# input_buff.net
KiCad netlist of a schematic drawn in EAGLE
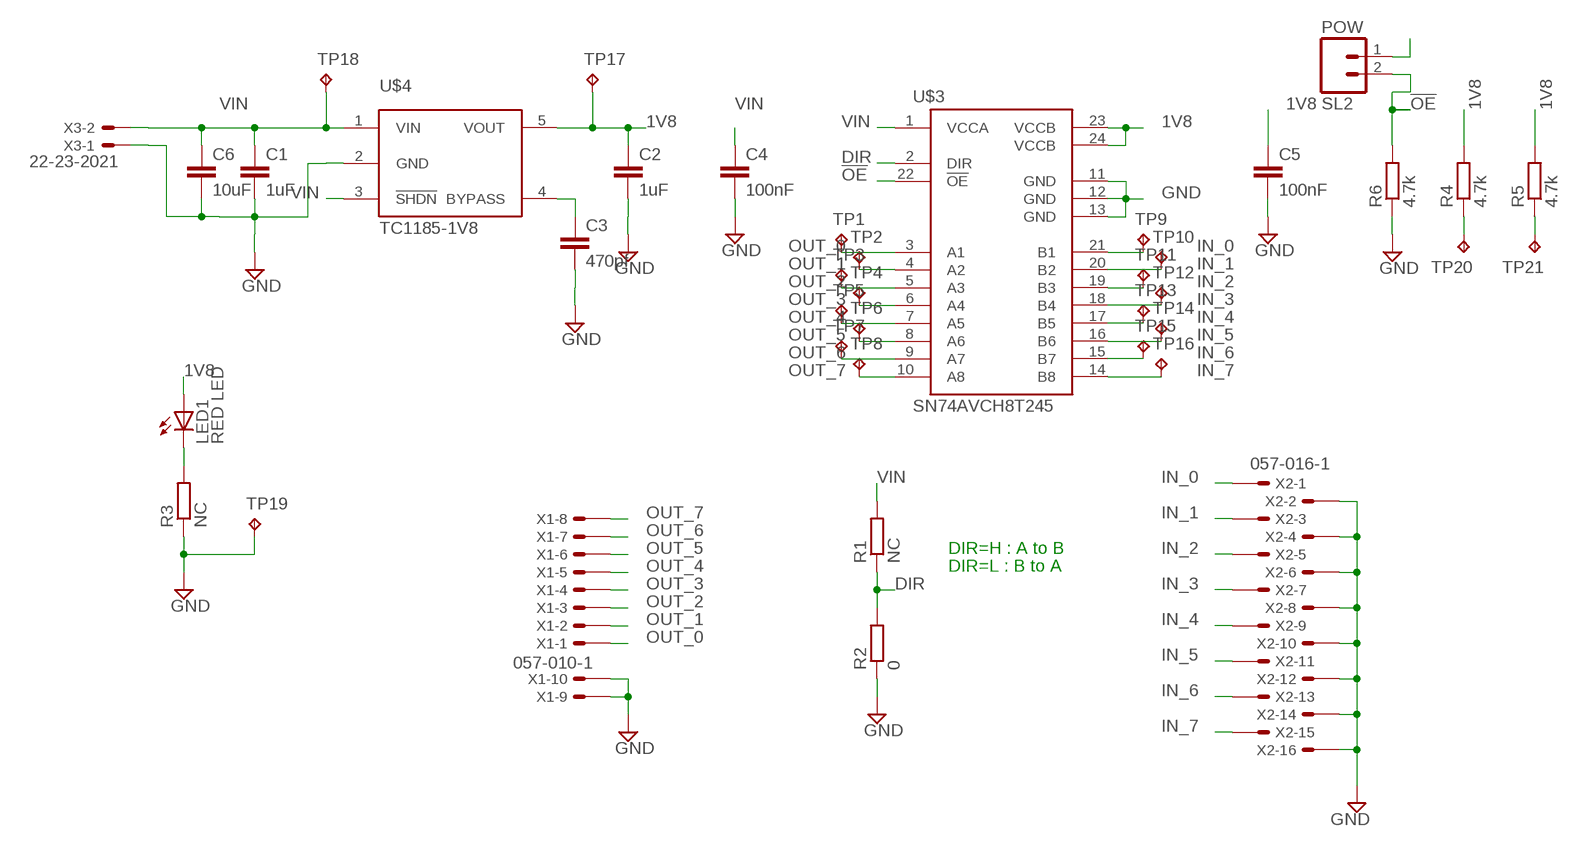
[diagram p0: schematic, sheet 1]

(export (version "E")
  (design (tool "Eeschema 10.0.6"))
  (components
    (comp (ref "C1")
      (value "1uF")
      (footprint "eagle-import:C0805")
      (libsource (lib "eagle-import") (part "C-EUC0805"))
    )
    (comp (ref "C2")
      (value "1uF")
      (footprint "eagle-import:C0805")
      (libsource (lib "eagle-import") (part "C-EUC0805"))
    )
    (comp (ref "C3")
      (value "470pf")
      (footprint "eagle-import:C0805")
      (libsource (lib "eagle-import") (part "C-EUC0805"))
    )
    (comp (ref "C4")
      (value "100nF")
      (footprint "eagle-import:C0805")
      (libsource (lib "eagle-import") (part "C-EUC0805"))
    )
    (comp (ref "C5")
      (value "100nF")
      (footprint "eagle-import:C0805")
      (libsource (lib "eagle-import") (part "C-EUC0805"))
    )
    (comp (ref "C6")
      (value "10uF")
      (footprint "eagle-import:C1210")
      (libsource (lib "eagle-import") (part "C-EUC1210"))
    )
    (comp (ref "LED1")
      (value "RED LED")
      (footprint "eagle-import:CHIPLED_0805")
      (libsource (lib "eagle-import") (part "LEDCHIPLED_0805"))
    )
    (comp (ref "R1")
      (value "NC")
      (footprint "eagle-import:M0805")
      (libsource (lib "eagle-import") (part "R-EU_M0805"))
    )
    (comp (ref "R2")
      (value "0")
      (footprint "eagle-import:M0805")
      (libsource (lib "eagle-import") (part "R-EU_M0805"))
    )
    (comp (ref "R3")
      (value "NC")
      (footprint "eagle-import:M0805")
      (libsource (lib "eagle-import") (part "R-EU_M0805"))
    )
    (comp (ref "R4")
      (value "4.7k")
      (footprint "eagle-import:M0805")
      (libsource (lib "eagle-import") (part "R-EU_M0805"))
    )
    (comp (ref "R5")
      (value "4.7k")
      (footprint "eagle-import:M0805")
      (libsource (lib "eagle-import") (part "R-EU_M0805"))
    )
    (comp (ref "R6")
      (value "4.7k")
      (footprint "eagle-import:M0805")
      (libsource (lib "eagle-import") (part "R-EU_M0805"))
    )
    (comp (ref "SL2")
      (value "POW")
      (footprint "eagle-import:02P")
      (fields (field (name "OC_FARNELL") "unknown") (field (name "OC_NEWARK") "unknown"))
      (libsource (lib "eagle-import") (part "M02"))
    )
    (comp (ref "TP1")
      (value "TPTP10R")
      (footprint "eagle-import:TP10R")
      (libsource (lib "eagle-import") (part "TPTP10R"))
    )
    (comp (ref "TP2")
      (value "TPTP10R")
      (footprint "eagle-import:TP10R")
      (libsource (lib "eagle-import") (part "TPTP10R"))
    )
    (comp (ref "TP3")
      (value "TPTP10R")
      (footprint "eagle-import:TP10R")
      (libsource (lib "eagle-import") (part "TPTP10R"))
    )
    (comp (ref "TP4")
      (value "TPTP10R")
      (footprint "eagle-import:TP10R")
      (libsource (lib "eagle-import") (part "TPTP10R"))
    )
    (comp (ref "TP5")
      (value "TPTP10R")
      (footprint "eagle-import:TP10R")
      (libsource (lib "eagle-import") (part "TPTP10R"))
    )
    (comp (ref "TP6")
      (value "TPTP10R")
      (footprint "eagle-import:TP10R")
      (libsource (lib "eagle-import") (part "TPTP10R"))
    )
    (comp (ref "TP7")
      (value "TPTP10R")
      (footprint "eagle-import:TP10R")
      (libsource (lib "eagle-import") (part "TPTP10R"))
    )
    (comp (ref "TP8")
      (value "TPTP10R")
      (footprint "eagle-import:TP10R")
      (libsource (lib "eagle-import") (part "TPTP10R"))
    )
    (comp (ref "TP9")
      (value "TPTP10R")
      (footprint "eagle-import:TP10R")
      (libsource (lib "eagle-import") (part "TPTP10R"))
    )
    (comp (ref "TP10")
      (value "TPTP10R")
      (footprint "eagle-import:TP10R")
      (libsource (lib "eagle-import") (part "TPTP10R"))
    )
    (comp (ref "TP11")
      (value "TPTP10R")
      (footprint "eagle-import:TP10R")
      (libsource (lib "eagle-import") (part "TPTP10R"))
    )
    (comp (ref "TP12")
      (value "TPTP10R")
      (footprint "eagle-import:TP10R")
      (libsource (lib "eagle-import") (part "TPTP10R"))
    )
    (comp (ref "TP13")
      (value "TPTP10R")
      (footprint "eagle-import:TP10R")
      (libsource (lib "eagle-import") (part "TPTP10R"))
    )
    (comp (ref "TP14")
      (value "TPTP10R")
      (footprint "eagle-import:TP10R")
      (libsource (lib "eagle-import") (part "TPTP10R"))
    )
    (comp (ref "TP15")
      (value "TPTP10R")
      (footprint "eagle-import:TP10R")
      (libsource (lib "eagle-import") (part "TPTP10R"))
    )
    (comp (ref "TP16")
      (value "TPTP10R")
      (footprint "eagle-import:TP10R")
      (libsource (lib "eagle-import") (part "TPTP10R"))
    )
    (comp (ref "TP17")
      (value "TPTP10R")
      (footprint "eagle-import:TP10R")
      (libsource (lib "eagle-import") (part "TPTP10R"))
    )
    (comp (ref "TP18")
      (value "TPTP10R")
      (footprint "eagle-import:TP10R")
      (libsource (lib "eagle-import") (part "TPTP10R"))
    )
    (comp (ref "TP19")
      (value "TPTP10R")
      (footprint "eagle-import:TP10R")
      (libsource (lib "eagle-import") (part "TPTP10R"))
    )
    (comp (ref "TP20")
      (value "TPTP10R")
      (footprint "eagle-import:TP10R")
      (libsource (lib "eagle-import") (part "TPTP10R"))
    )
    (comp (ref "TP21")
      (value "TPTP10R")
      (footprint "eagle-import:TP10R")
      (libsource (lib "eagle-import") (part "TPTP10R"))
    )
    (comp (ref "U$3")
      (value "SN74AVCH8T245")
      (footprint "eagle-import:TSSOP24")
      (fields (field (name "MF") "TEXAS INSTRUMENTS"))
      (libsource (lib "eagle-import") (part "SN74AVCH8T245"))
    )
    (comp (ref "U$4")
      (value "TC1185-1V8")
      (footprint "eagle-import:SOT23-5")
      (libsource (lib "eagle-import") (part "TC1185-1V8"))
    )
    (comp (ref "X1")
      (value "057-010-1")
      (footprint "eagle-import:057-010-1")
      (libsource (lib "eagle-import") (part "057-010-1"))
    )
    (comp (ref "X2")
      (value "057-016-1")
      (footprint "eagle-import:057-016-1")
      (libsource (lib "eagle-import") (part "057-016-1"))
    )
    (comp (ref "X3")
      (value "22-23-2021")
      (footprint "eagle-import:22-23-2021")
      (fields (field (name "MF") "MOLEX"))
      (libsource (lib "eagle-import") (part "22-23-2021"))
    )
  )
  (nets
    (net (code "1") (name "/1V8") (class "Default")
      (node (ref "C2") (pin "1") (pinfunction "1_1") (pintype "passive"))
      (node (ref "C5") (pin "1") (pinfunction "1_1") (pintype "passive"))
      (node (ref "LED1") (pin "A") (pinfunction "A_A") (pintype "passive"))
      (node (ref "R4") (pin "2") (pinfunction "2_2") (pintype "passive"))
      (node (ref "R5") (pin "2") (pinfunction "2_2") (pintype "passive"))
      (node (ref "TP17") (pin "TP") (pinfunction "TP_TP") (pintype "input"))
      (node (ref "U$3") (pin "23") (pinfunction "VCCB_23") (pintype "bidirectional"))
      (node (ref "U$3") (pin "24") (pinfunction "VCCB_24") (pintype "bidirectional"))
      (node (ref "U$4") (pin "5") (pinfunction "VOUT_5") (pintype "power_in"))
    )
    (net (code "2") (name "/DIR") (class "Default")
      (node (ref "R1") (pin "1") (pinfunction "1_1") (pintype "passive"))
      (node (ref "R2") (pin "2") (pinfunction "2_2") (pintype "passive"))
      (node (ref "U$3") (pin "2") (pinfunction "DIR_2") (pintype "bidirectional"))
    )
    (net (code "3") (name "/IN_0") (class "Default")
      (node (ref "TP9") (pin "TP") (pinfunction "TP_TP") (pintype "input"))
      (node (ref "U$3") (pin "21") (pinfunction "B1_21") (pintype "bidirectional"))
      (node (ref "X2") (pin "1") (pinfunction "S_1") (pintype "passive"))
    )
    (net (code "4") (name "/IN_1") (class "Default")
      (node (ref "TP10") (pin "TP") (pinfunction "TP_TP") (pintype "input"))
      (node (ref "U$3") (pin "20") (pinfunction "B2_20") (pintype "bidirectional"))
      (node (ref "X2") (pin "3") (pinfunction "S_3") (pintype "passive"))
    )
    (net (code "5") (name "/IN_2") (class "Default")
      (node (ref "TP11") (pin "TP") (pinfunction "TP_TP") (pintype "input"))
      (node (ref "U$3") (pin "19") (pinfunction "B3_19") (pintype "bidirectional"))
      (node (ref "X2") (pin "5") (pinfunction "S_5") (pintype "passive"))
    )
    (net (code "6") (name "/IN_3") (class "Default")
      (node (ref "TP12") (pin "TP") (pinfunction "TP_TP") (pintype "input"))
      (node (ref "U$3") (pin "18") (pinfunction "B4_18") (pintype "bidirectional"))
      (node (ref "X2") (pin "7") (pinfunction "S_7") (pintype "passive"))
    )
    (net (code "7") (name "/IN_4") (class "Default")
      (node (ref "TP13") (pin "TP") (pinfunction "TP_TP") (pintype "input"))
      (node (ref "U$3") (pin "17") (pinfunction "B5_17") (pintype "bidirectional"))
      (node (ref "X2") (pin "9") (pinfunction "S_9") (pintype "passive"))
    )
    (net (code "8") (name "/IN_5") (class "Default")
      (node (ref "TP14") (pin "TP") (pinfunction "TP_TP") (pintype "input"))
      (node (ref "U$3") (pin "16") (pinfunction "B6_16") (pintype "bidirectional"))
      (node (ref "X2") (pin "11") (pinfunction "S_11") (pintype "passive"))
    )
    (net (code "9") (name "/IN_6") (class "Default")
      (node (ref "TP15") (pin "TP") (pinfunction "TP_TP") (pintype "input"))
      (node (ref "U$3") (pin "15") (pinfunction "B7_15") (pintype "bidirectional"))
      (node (ref "X2") (pin "13") (pinfunction "S_13") (pintype "passive"))
    )
    (net (code "10") (name "/IN_7") (class "Default")
      (node (ref "TP16") (pin "TP") (pinfunction "TP_TP") (pintype "input"))
      (node (ref "U$3") (pin "14") (pinfunction "B8_14") (pintype "bidirectional"))
      (node (ref "X2") (pin "15") (pinfunction "S_15") (pintype "passive"))
    )
    (net (code "11") (name "/OUT_0") (class "Default")
      (node (ref "TP1") (pin "TP") (pinfunction "TP_TP") (pintype "input"))
      (node (ref "U$3") (pin "3") (pinfunction "A1_3") (pintype "bidirectional"))
      (node (ref "X1") (pin "1") (pinfunction "S_1") (pintype "passive"))
    )
    (net (code "12") (name "/OUT_1") (class "Default")
      (node (ref "TP2") (pin "TP") (pinfunction "TP_TP") (pintype "input"))
      (node (ref "U$3") (pin "4") (pinfunction "A2_4") (pintype "bidirectional"))
      (node (ref "X1") (pin "2") (pinfunction "S_2") (pintype "passive"))
    )
    (net (code "13") (name "/OUT_2") (class "Default")
      (node (ref "TP3") (pin "TP") (pinfunction "TP_TP") (pintype "input"))
      (node (ref "U$3") (pin "5") (pinfunction "A3_5") (pintype "bidirectional"))
      (node (ref "X1") (pin "3") (pinfunction "S_3") (pintype "passive"))
    )
    (net (code "14") (name "/OUT_3") (class "Default")
      (node (ref "TP4") (pin "TP") (pinfunction "TP_TP") (pintype "input"))
      (node (ref "U$3") (pin "6") (pinfunction "A4_6") (pintype "bidirectional"))
      (node (ref "X1") (pin "4") (pinfunction "S_4") (pintype "passive"))
    )
    (net (code "15") (name "/OUT_4") (class "Default")
      (node (ref "TP5") (pin "TP") (pinfunction "TP_TP") (pintype "input"))
      (node (ref "U$3") (pin "7") (pinfunction "A5_7") (pintype "bidirectional"))
      (node (ref "X1") (pin "5") (pinfunction "S_5") (pintype "passive"))
    )
    (net (code "16") (name "/OUT_5") (class "Default")
      (node (ref "TP6") (pin "TP") (pinfunction "TP_TP") (pintype "input"))
      (node (ref "U$3") (pin "8") (pinfunction "A6_8") (pintype "bidirectional"))
      (node (ref "X1") (pin "6") (pinfunction "S_6") (pintype "passive"))
    )
    (net (code "17") (name "/OUT_6") (class "Default")
      (node (ref "TP7") (pin "TP") (pinfunction "TP_TP") (pintype "input"))
      (node (ref "U$3") (pin "9") (pinfunction "A7_9") (pintype "bidirectional"))
      (node (ref "X1") (pin "7") (pinfunction "S_7") (pintype "passive"))
    )
    (net (code "18") (name "/OUT_7") (class "Default")
      (node (ref "TP8") (pin "TP") (pinfunction "TP_TP") (pintype "input"))
      (node (ref "U$3") (pin "10") (pinfunction "A8_10") (pintype "bidirectional"))
      (node (ref "X1") (pin "8") (pinfunction "S_8") (pintype "passive"))
    )
    (net (code "19") (name "/VIN") (class "Default")
      (node (ref "C1") (pin "1") (pinfunction "1_1") (pintype "passive"))
      (node (ref "C4") (pin "1") (pinfunction "1_1") (pintype "passive"))
      (node (ref "C6") (pin "1") (pinfunction "1_1") (pintype "passive"))
      (node (ref "R1") (pin "2") (pinfunction "2_2") (pintype "passive"))
      (node (ref "SL2") (pin "1") (pinfunction "1_1") (pintype "passive"))
      (node (ref "TP18") (pin "TP") (pinfunction "TP_TP") (pintype "input"))
      (node (ref "U$3") (pin "1") (pinfunction "VCCA_1") (pintype "bidirectional"))
      (node (ref "U$4") (pin "1") (pinfunction "VIN_1") (pintype "power_in"))
      (node (ref "U$4") (pin "3") (pinfunction "~{SHDN}_3") (pintype "bidirectional"))
      (node (ref "X3") (pin "2") (pinfunction "S_2") (pintype "passive"))
    )
    (net (code "20") (name "/~{OE}") (class "Default")
      (node (ref "R6") (pin "2") (pinfunction "2_2") (pintype "passive"))
      (node (ref "SL2") (pin "2") (pinfunction "2_2") (pintype "passive"))
      (node (ref "U$3") (pin "22") (pinfunction "~{OE}_22") (pintype "bidirectional"))
    )
    (net (code "21") (name "GND") (class "Default")
      (node (ref "C1") (pin "2") (pinfunction "2_2") (pintype "passive"))
      (node (ref "C2") (pin "2") (pinfunction "2_2") (pintype "passive"))
      (node (ref "C3") (pin "2") (pinfunction "2_2") (pintype "passive"))
      (node (ref "C4") (pin "2") (pinfunction "2_2") (pintype "passive"))
      (node (ref "C5") (pin "2") (pinfunction "2_2") (pintype "passive"))
      (node (ref "C6") (pin "2") (pinfunction "2_2") (pintype "passive"))
      (node (ref "R2") (pin "1") (pinfunction "1_1") (pintype "passive"))
      (node (ref "R3") (pin "1") (pinfunction "1_1") (pintype "passive"))
      (node (ref "R6") (pin "1") (pinfunction "1_1") (pintype "passive"))
      (node (ref "TP19") (pin "TP") (pinfunction "TP_TP") (pintype "input"))
      (node (ref "U$3") (pin "11") (pinfunction "GND_11") (pintype "bidirectional"))
      (node (ref "U$3") (pin "12") (pinfunction "GND_12") (pintype "bidirectional"))
      (node (ref "U$3") (pin "13") (pinfunction "GND_13") (pintype "bidirectional"))
      (node (ref "U$4") (pin "2") (pinfunction "GND_2") (pintype "power_in"))
      (node (ref "X1") (pin "10") (pinfunction "S_10") (pintype "passive"))
      (node (ref "X1") (pin "9") (pinfunction "S_9") (pintype "passive"))
      (node (ref "X2") (pin "10") (pinfunction "S_10") (pintype "passive"))
      (node (ref "X2") (pin "12") (pinfunction "S_12") (pintype "passive"))
      (node (ref "X2") (pin "14") (pinfunction "S_14") (pintype "passive"))
      (node (ref "X2") (pin "16") (pinfunction "S_16") (pintype "passive"))
      (node (ref "X2") (pin "2") (pinfunction "S_2") (pintype "passive"))
      (node (ref "X2") (pin "4") (pinfunction "S_4") (pintype "passive"))
      (node (ref "X2") (pin "6") (pinfunction "S_6") (pintype "passive"))
      (node (ref "X2") (pin "8") (pinfunction "S_8") (pintype "passive"))
      (node (ref "X3") (pin "1") (pinfunction "S_1") (pintype "passive"))
    )
    (net (code "22") (name "Net-(LED1-PadC)") (class "Default")
      (node (ref "LED1") (pin "C") (pinfunction "C_C") (pintype "passive"))
      (node (ref "R3") (pin "2") (pinfunction "2_2") (pintype "passive"))
    )
    (net (code "23") (name "Net-(R4-Pad1)") (class "Default")
      (node (ref "R4") (pin "1") (pinfunction "1_1") (pintype "passive"))
      (node (ref "TP20") (pin "TP") (pinfunction "TP_TP") (pintype "input"))
    )
    (net (code "24") (name "Net-(R5-Pad1)") (class "Default")
      (node (ref "R5") (pin "1") (pinfunction "1_1") (pintype "passive"))
      (node (ref "TP21") (pin "TP") (pinfunction "TP_TP") (pintype "input"))
    )
    (net (code "25") (name "Net-(U$4-BYPASS)") (class "Default")
      (node (ref "C3") (pin "1") (pinfunction "1_1") (pintype "passive"))
      (node (ref "U$4") (pin "4") (pinfunction "BYPASS_4") (pintype "bidirectional"))
    )
  )
)
